# BOOT_JTAG_AUX.net
KiCad netlist of a schematic drawn in Altium Designer
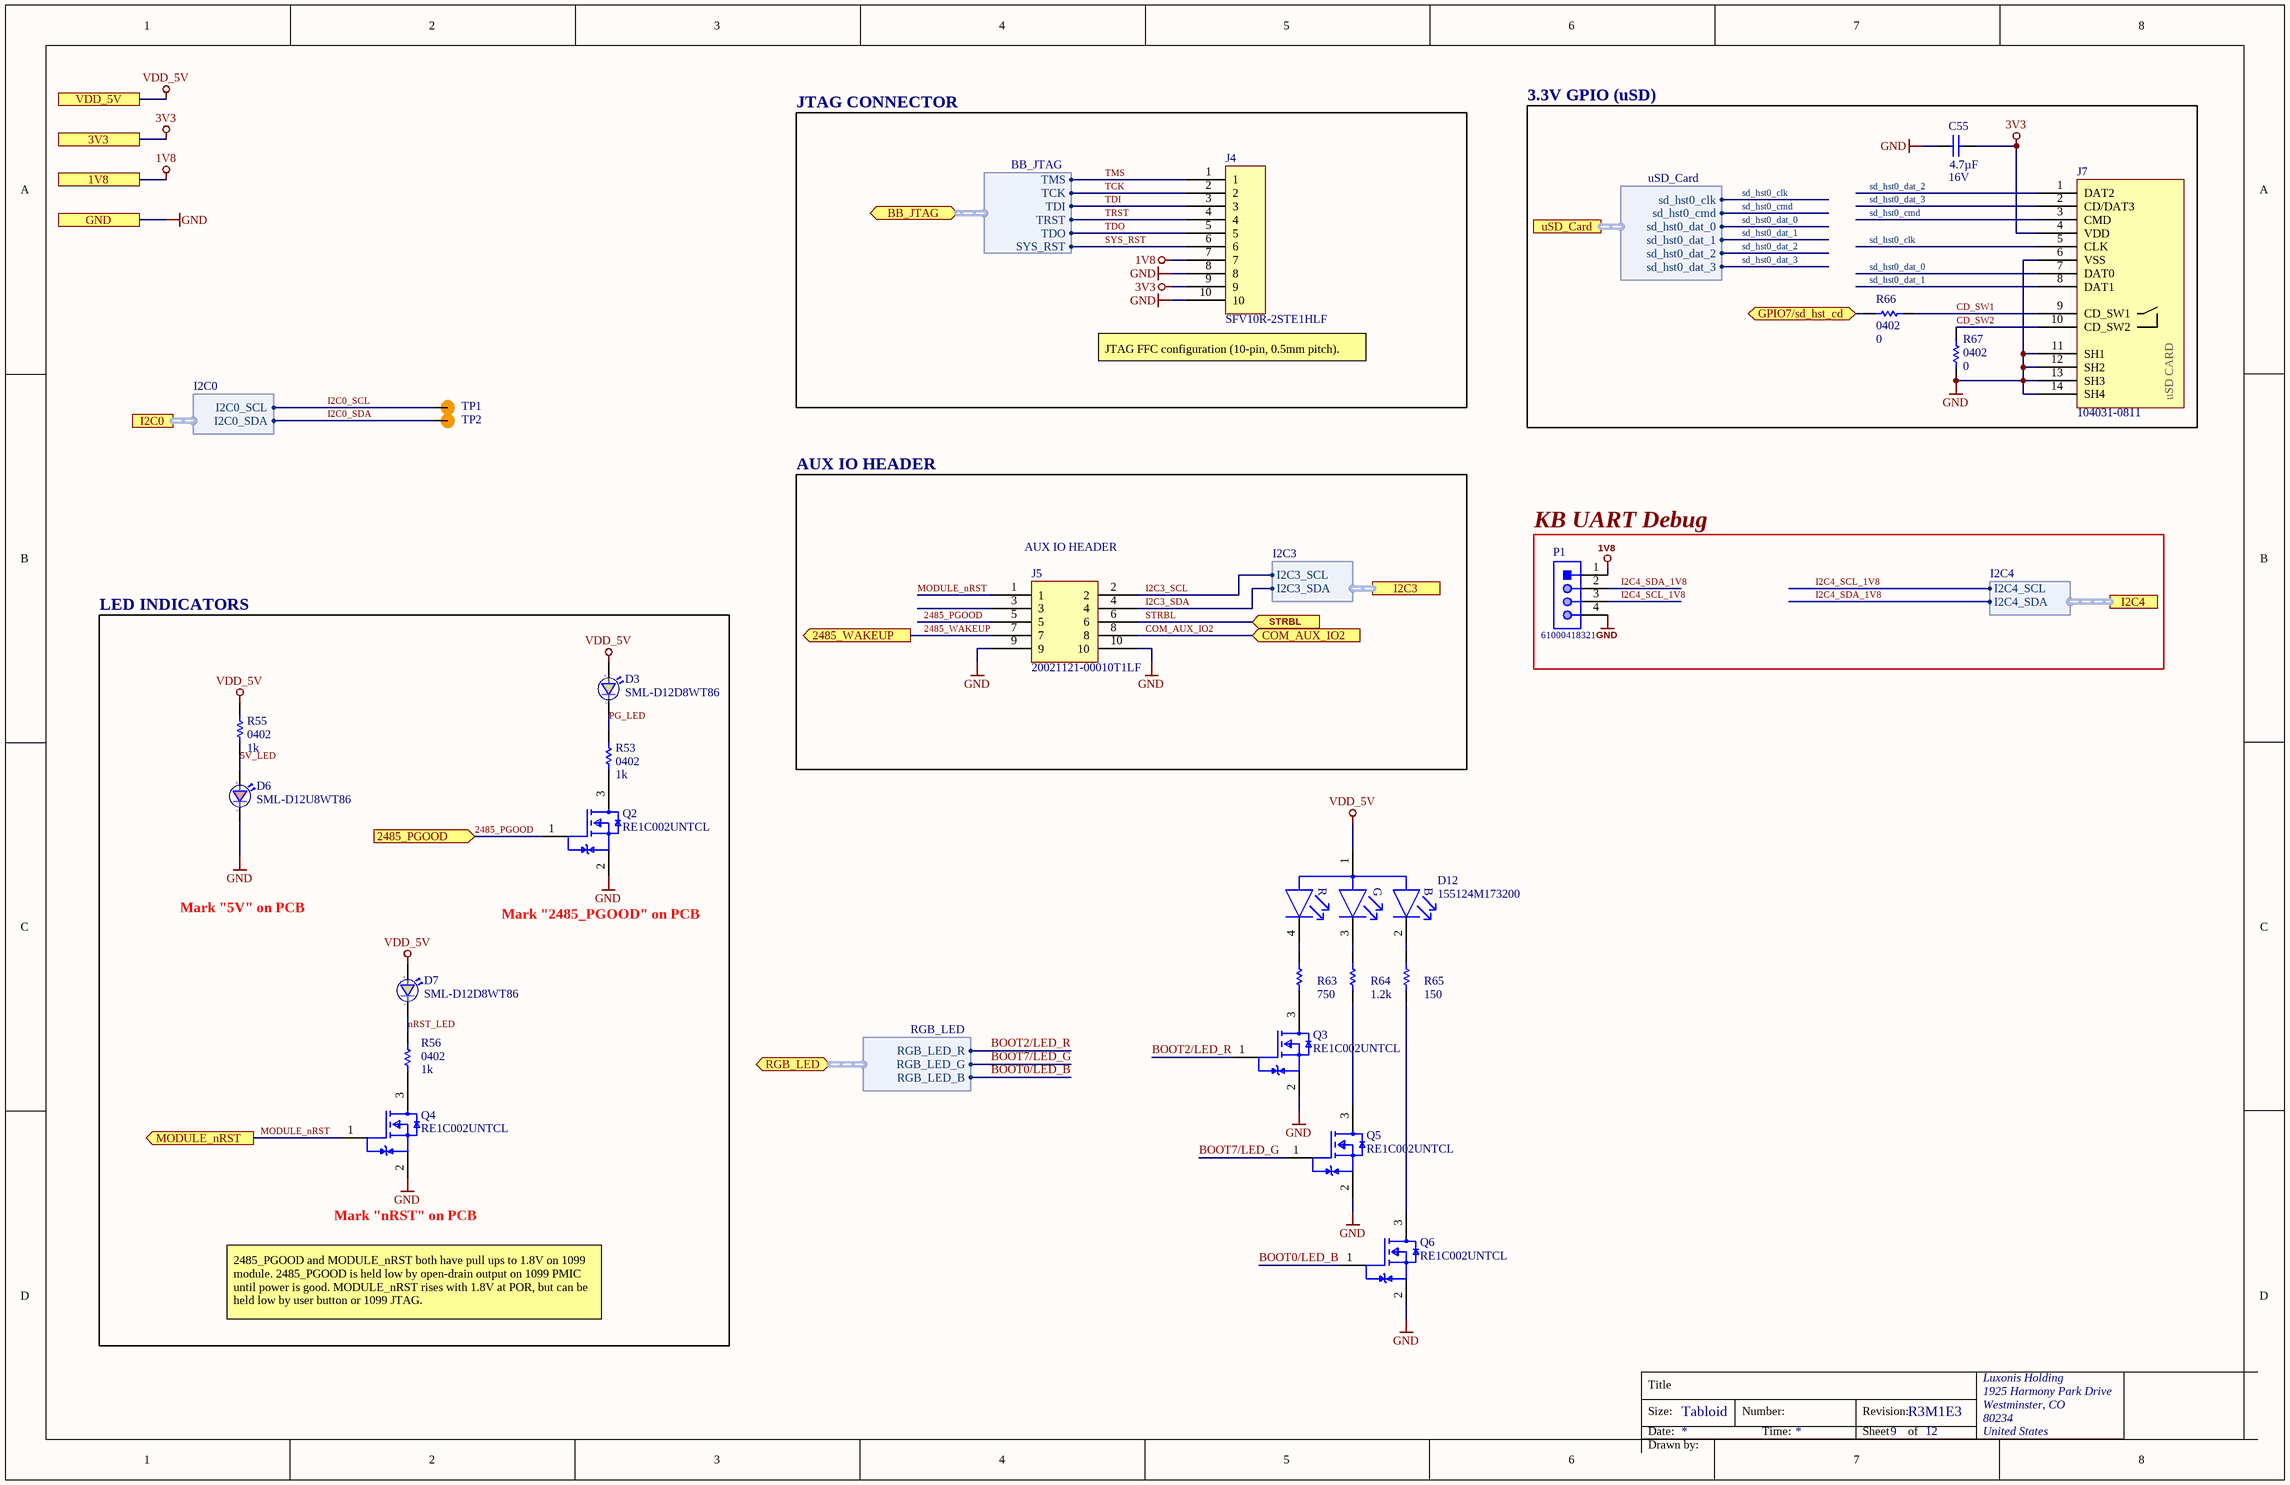
[diagram p0: BOOT_JTAG_AUX.SchDoc]

(export (version "E")
  (design (tool "Eeschema 10.0.6"))
  (components
    (comp (ref "C55")
      (value "4.7µF")
      (footprint "CAPC0603(1608)100_N")
      (description "CAP CER 4.7UF 16V X5R 0603 10%")
      (fields
        (field (name "TOLERANCE") "10%")
        (field (name "VOLTAGE RATING") "16V")
        (field (name "Comment") "GRM188R61C475KAAJD")
      )
      (libsource (lib "Luxonis LLC") (part "LLL153C70G474ME17E"))
    )
    (comp (ref "D3")
      (value "SML-D12D8WT86")
      (footprint "SML_D1xx8W")
      (description "LED ORANGE DIFFUSED 0603 SMD Orange 605nm LED Indication - Discrete 2.2V 0603 (1608 Metric)")
      (libsource (lib "Luxonis LLC") (part "SML-D12D8WT86"))
    )
    (comp (ref "D6")
      (value "SML-D12U8WT86")
      (footprint "SML_D1xx8W")
      (description "LED RED DIFFUSED 0603 SMD Red 620nm LED Indication - Discrete 2.2V 0603 (1608 Metric)")
      (libsource (lib "Luxonis LLC") (part "SML-D12U8WT86"))
    )
    (comp (ref "D7")
      (value "SML-D12D8WT86")
      (footprint "SML_D1xx8W")
      (description "LED ORANGE DIFFUSED 0603 SMD Orange 605nm LED Indication - Discrete 2.2V 0603 (1608 Metric)")
      (libsource (lib "Luxonis LLC") (part "SML-D12D8WT86"))
    )
    (comp (ref "D12")
      (value "155124M173200")
      (footprint "FP-155124M173200-MFG")
      (description "Triple Color LED")
      (libsource (lib "Luxonis LLC") (part "8635049b720462866f33dfa80272b1c"))
    )
    (comp (ref "J4")
      (value "SFV10R-2STE1HLF")
      (footprint "SFV10R-2STE1HLF")
      (description "CONN FFC TOP 10POS 0.50MM R/A")
      (libsource (lib "Luxonis LLC") (part "SFV10R-2STE1HLF"))
    )
    (comp (ref "J5")
      (value "20021121-00010T1LF")
      (footprint "20021121-00010T1LF")
      (description "CONN HEADER SMD 10POS 1.27MM")
      (libsource (lib "Luxonis LLC") (part "20021121-00010T1LF"))
    )
    (comp (ref "J7")
      (value "104031-0811")
      (footprint "104031-0811")
      (description "CONN MICRO SD CARD PUSH-PULL R/A")
      (libsource (lib "Luxonis LLC") (part "104031-0811"))
    )
    (comp (ref "P1")
      (value "61000418321")
      (footprint "61000418321")
      (description "Terminal and Terminal Block")
      (libsource (lib "Luxonis LLC") (part "WE-CN-1P-M-R4"))
    )
    (comp (ref "Q2")
      (value "RE1C002UNTCL")
      (footprint "RE1C002UNTCL")
      (description "MOSFET N-CH 20V 0.2A EMT3")
      (libsource (lib "Luxonis LLC") (part "RE1C002UNTCL"))
    )
    (comp (ref "Q3")
      (value "RE1C002UNTCL")
      (footprint "RE1C002UNTCL")
      (description "MOSFET N-CH 20V 0.2A EMT3")
      (libsource (lib "Luxonis LLC") (part "RE1C002UNTCL"))
    )
    (comp (ref "Q4")
      (value "RE1C002UNTCL")
      (footprint "RE1C002UNTCL")
      (description "MOSFET N-CH 20V 0.2A EMT3")
      (libsource (lib "Luxonis LLC") (part "RE1C002UNTCL"))
    )
    (comp (ref "Q5")
      (value "RE1C002UNTCL")
      (footprint "RE1C002UNTCL")
      (description "MOSFET N-CH 20V 0.2A EMT3")
      (libsource (lib "Luxonis LLC") (part "RE1C002UNTCL"))
    )
    (comp (ref "Q6")
      (value "RE1C002UNTCL")
      (footprint "RE1C002UNTCL")
      (description "MOSFET N-CH 20V 0.2A EMT3")
      (libsource (lib "Luxonis LLC") (part "RE1C002UNTCL"))
    )
    (comp (ref "R53")
      (value "1k")
      (footprint "RESC0402(1005)_N")
      (description "RES SMD 1K OHM 1% 1/16W 0402")
      (fields
        (field (name "CASE/PACKAGE") "0402")
        (field (name "TOLERANCE") "1%")
        (field (name "Comment") "RC0402FR-071KL")
      )
      (libsource (lib "Luxonis LLC") (part "Default resistor symbol"))
    )
    (comp (ref "R55")
      (value "1k")
      (footprint "RESC0402(1005)_N")
      (description "RES SMD 1K OHM 1% 1/16W 0402")
      (fields
        (field (name "CASE/PACKAGE") "0402")
        (field (name "TOLERANCE") "1%")
        (field (name "Comment") "RC0402FR-071KL")
      )
      (libsource (lib "Luxonis LLC") (part "Default resistor symbol"))
    )
    (comp (ref "R56")
      (value "1k")
      (footprint "RESC0402(1005)_N")
      (description "RES SMD 1K OHM 1% 1/16W 0402")
      (fields
        (field (name "CASE/PACKAGE") "0402")
        (field (name "TOLERANCE") "1%")
        (field (name "Comment") "RC0402FR-071KL")
      )
      (libsource (lib "Luxonis LLC") (part "Default resistor symbol"))
    )
    (comp (ref "R63")
      (value "750")
      (footprint "RESC1005X40X25NL05T05")
      (description "RES SMD 750 OHM 1% 0.1W 0402")
      (fields (field (name "TOLERANCE") "1%") (field (name "Comment") "ERJ-2RKF7500X"))
      (libsource (lib "Luxonis LLC") (part "Default resistor symbol"))
    )
    (comp (ref "R64")
      (value "1.2k")
      (footprint "RESC1005X40X25NL05T05")
      (description "RES SMD 1.2K OHM 1% 0.063W 0402")
      (fields (field (name "TOLERANCE") "1%") (field (name "Comment") "CRCW04021K20FKED"))
      (libsource (lib "Luxonis LLC") (part "Default resistor symbol"))
    )
    (comp (ref "R65")
      (value "150")
      (footprint "RESC1005X40X25NL05T10")
      (description "RES SMD 150 OHM 1% 1/16W 0402")
      (fields (field (name "TOLERANCE") "1%") (field (name "Comment") "RC0402FR-07150RL"))
      (libsource (lib "Luxonis LLC") (part "Default resistor symbol"))
    )
    (comp (ref "R66")
      (value "0")
      (footprint "RESC0402(1005)_N")
      (description "RES SMD 0 OHM 5% 1/16W 0402")
      (fields
        (field (name "CASE/PACKAGE") "0402")
        (field (name "TOLERANCE") "5%")
        (field (name "Comment") "CRCW04020000Z0ED")
      )
      (libsource (lib "Luxonis LLC") (part "Default resistor symbol"))
    )
    (comp (ref "R67")
      (value "0")
      (footprint "RESC0402(1005)_N")
      (description "RES SMD 0 OHM 5% 1/16W 0402")
      (fields
        (field (name "CASE/PACKAGE") "0402")
        (field (name "TOLERANCE") "5%")
        (field (name "Comment") "CRCW04020000Z0ED")
      )
      (libsource (lib "Luxonis LLC") (part "Default resistor symbol"))
    )
    (comp (ref "TP1")
      (value "TEST_POINT")
      (footprint "TP100_200_NS")
      (libsource (lib "Luxonis LLC") (part "TEST_POINT"))
    )
    (comp (ref "TP2")
      (value "TEST_POINT")
      (footprint "TP100_200_NS")
      (libsource (lib "Luxonis LLC") (part "TEST_POINT"))
    )
  )
  (nets
    (net (code "7") (name "/5V_LED") (class "Default")
      (node (ref "D6") (pin "2") (pinfunction "A_2") (pintype "passive"))
      (node (ref "R55") (pin "1") (pinfunction "1_1") (pintype "passive"))
    )
    (net (code "8") (name "/2485_PGOOD") (class "Default")
      (node (ref "J5") (pin "5") (pinfunction "5_5") (pintype "passive"))
      (node (ref "Q2") (pin "1") (pinfunction "Gate_1") (pintype "passive"))
    )
    (net (code "9") (name "/2485_WAKEUP") (class "Default")
      (node (ref "J5") (pin "7") (pinfunction "7_7") (pintype "passive"))
    )
    (net (code "10") (name "/BOOT0{slash}LED_B") (class "Default")
      (node (ref "Q6") (pin "1") (pinfunction "Gate_1") (pintype "passive"))
    )
    (net (code "11") (name "/BOOT2{slash}LED_R") (class "Default")
      (node (ref "Q3") (pin "1") (pinfunction "Gate_1") (pintype "passive"))
    )
    (net (code "12") (name "/BOOT7{slash}LED_G") (class "Default")
      (node (ref "Q5") (pin "1") (pinfunction "Gate_1") (pintype "passive"))
    )
    (net (code "13") (name "/CD_SW1") (class "Default")
      (node (ref "J7") (pin "9") (pinfunction "CD_SW1_9") (pintype "passive"))
      (node (ref "R66") (pin "1") (pinfunction "1_1") (pintype "passive"))
    )
    (net (code "14") (name "/CD_SW2") (class "Default")
      (node (ref "J7") (pin "10") (pinfunction "CD_SW2_10") (pintype "passive"))
      (node (ref "R67") (pin "2") (pinfunction "2_2") (pintype "passive"))
    )
    (net (code "15") (name "/COM_AUX_IO2") (class "Default")
      (node (ref "J5") (pin "8") (pinfunction "8_8") (pintype "passive"))
    )
    (net (code "16") (name "/GPIO7{slash}sd_hst_cd") (class "Default")
      (node (ref "R66") (pin "2") (pinfunction "2_2") (pintype "passive"))
    )
    (net (code "17") (name "/I2C0_SCL") (class "Default") (node (ref "TP1") (pin "1") (pintype "passive")))
    (net (code "18") (name "/I2C0_SDA") (class "Default") (node (ref "TP2") (pin "1") (pintype "passive")))
    (net (code "19") (name "/I2C3_SCL") (class "Default")
      (node (ref "J5") (pin "2") (pinfunction "2_2") (pintype "passive"))
    )
    (net (code "20") (name "/I2C3_SDA") (class "Default")
      (node (ref "J5") (pin "4") (pinfunction "4_4") (pintype "passive"))
    )
    (net (code "21") (name "/I2C4_SCL_1V8") (class "Default")
      (node (ref "P1") (pin "3") (pinfunction "3_3") (pintype "passive"))
    )
    (net (code "22") (name "/I2C4_SDA_1V8") (class "Default")
      (node (ref "P1") (pin "2") (pinfunction "2_2") (pintype "passive"))
    )
    (net (code "23") (name "/MODULE_nRST") (class "Default")
      (node (ref "J5") (pin "1") (pinfunction "1_1") (pintype "passive"))
      (node (ref "Q4") (pin "1") (pinfunction "Gate_1") (pintype "passive"))
    )
    (net (code "24") (name "/PG_LED") (class "Default")
      (node (ref "D3") (pin "1") (pinfunction "C_1") (pintype "passive"))
      (node (ref "R53") (pin "2") (pinfunction "2_2") (pintype "passive"))
    )
    (net (code "25") (name "/STRBL") (class "Default")
      (node (ref "J5") (pin "6") (pinfunction "6_6") (pintype "passive"))
    )
    (net (code "26") (name "/SYS_RST") (class "Default")
      (node (ref "J4") (pin "6") (pinfunction "6_6") (pintype "passive"))
    )
    (net (code "27") (name "/TCK") (class "Default")
      (node (ref "J4") (pin "2") (pinfunction "2_2") (pintype "passive"))
    )
    (net (code "28") (name "/TDI") (class "Default")
      (node (ref "J4") (pin "3") (pinfunction "3_3") (pintype "passive"))
    )
    (net (code "29") (name "/TDO") (class "Default")
      (node (ref "J4") (pin "5") (pinfunction "5_5") (pintype "passive"))
    )
    (net (code "30") (name "/TMS") (class "Default")
      (node (ref "J4") (pin "1") (pinfunction "1_1") (pintype "passive"))
    )
    (net (code "31") (name "/TRST") (class "Default")
      (node (ref "J4") (pin "4") (pinfunction "4_4") (pintype "passive"))
    )
    (net (code "32") (name "/nRST_LED") (class "Default")
      (node (ref "D7") (pin "1") (pinfunction "C_1") (pintype "passive"))
      (node (ref "R56") (pin "2") (pinfunction "2_2") (pintype "passive"))
    )
    (net (code "33") (name "/sd_hst0_clk") (class "Default")
      (node (ref "J7") (pin "5") (pinfunction "CLK_5") (pintype "passive"))
    )
    (net (code "34") (name "/sd_hst0_cmd") (class "Default")
      (node (ref "J7") (pin "3") (pinfunction "CMD_3") (pintype "passive"))
    )
    (net (code "35") (name "/sd_hst0_dat_0") (class "Default")
      (node (ref "J7") (pin "7") (pinfunction "DAT0_7") (pintype "passive"))
    )
    (net (code "36") (name "/sd_hst0_dat_1") (class "Default")
      (node (ref "J7") (pin "8") (pinfunction "DAT1_8") (pintype "passive"))
    )
    (net (code "37") (name "/sd_hst0_dat_2") (class "Default")
      (node (ref "J7") (pin "1") (pinfunction "DAT2_1") (pintype "passive"))
    )
    (net (code "38") (name "/sd_hst0_dat_3") (class "Default")
      (node (ref "J7") (pin "2") (pinfunction "CD/DAT3_2") (pintype "passive"))
    )
    (net (code "45") (name "1V8") (class "Default")
      (node (ref "J4") (pin "7") (pinfunction "7_7") (pintype "passive"))
      (node (ref "P1") (pin "1") (pinfunction "1_1") (pintype "passive"))
    )
    (net (code "46") (name "3V3") (class "Default")
      (node (ref "C55") (pin "2") (pinfunction "2_2") (pintype "passive"))
      (node (ref "J4") (pin "9") (pinfunction "9_9") (pintype "passive"))
      (node (ref "J7") (pin "4") (pinfunction "VDD_4") (pintype "passive"))
    )
    (net (code "47") (name "GND") (class "Default")
      (node (ref "C55") (pin "1") (pinfunction "1_1") (pintype "passive"))
      (node (ref "D6") (pin "1") (pinfunction "C_1") (pintype "passive"))
      (node (ref "J4") (pin "10") (pinfunction "10_10") (pintype "passive"))
      (node (ref "J4") (pin "8") (pinfunction "8_8") (pintype "passive"))
      (node (ref "J5") (pin "10") (pinfunction "10_10") (pintype "passive"))
      (node (ref "J5") (pin "9") (pinfunction "9_9") (pintype "passive"))
      (node (ref "J7") (pin "11") (pinfunction "SH1_11") (pintype "passive"))
      (node (ref "J7") (pin "12") (pinfunction "SH2_12") (pintype "passive"))
      (node (ref "J7") (pin "13") (pinfunction "SH3_13") (pintype "passive"))
      (node (ref "J7") (pin "14") (pinfunction "SH4_14") (pintype "passive"))
      (node (ref "J7") (pin "6") (pinfunction "VSS_6") (pintype "passive"))
      (node (ref "P1") (pin "4") (pinfunction "4_4") (pintype "passive"))
      (node (ref "Q2") (pin "2") (pinfunction "Source_2") (pintype "passive"))
      (node (ref "Q3") (pin "2") (pinfunction "Source_2") (pintype "passive"))
      (node (ref "Q4") (pin "2") (pinfunction "Source_2") (pintype "passive"))
      (node (ref "Q5") (pin "2") (pinfunction "Source_2") (pintype "passive"))
      (node (ref "Q6") (pin "2") (pinfunction "Source_2") (pintype "passive"))
      (node (ref "R67") (pin "1") (pinfunction "1_1") (pintype "passive"))
    )
    (net (code "48") (name "Net-(D12-BLUE_C)") (class "Default")
      (node (ref "D12") (pin "2") (pinfunction "BLUE_C_2") (pintype "passive"))
      (node (ref "R65") (pin "2") (pinfunction "2_2") (pintype "passive"))
    )
    (net (code "49") (name "Net-(D12-GREEN_C)") (class "Default")
      (node (ref "D12") (pin "3") (pinfunction "GREEN_C_3") (pintype "passive"))
      (node (ref "R64") (pin "2") (pinfunction "2_2") (pintype "passive"))
    )
    (net (code "50") (name "Net-(D12-RED_C)") (class "Default")
      (node (ref "D12") (pin "4") (pinfunction "RED_C_4") (pintype "passive"))
      (node (ref "R63") (pin "2") (pinfunction "2_2") (pintype "passive"))
    )
    (net (code "51") (name "Net-(Q2-Drain)") (class "Default")
      (node (ref "Q2") (pin "3") (pinfunction "Drain_3") (pintype "passive"))
      (node (ref "R53") (pin "1") (pinfunction "1_1") (pintype "passive"))
    )
    (net (code "52") (name "Net-(Q3-Drain)") (class "Default")
      (node (ref "Q3") (pin "3") (pinfunction "Drain_3") (pintype "passive"))
      (node (ref "R63") (pin "1") (pinfunction "1_1") (pintype "passive"))
    )
    (net (code "53") (name "Net-(Q4-Drain)") (class "Default")
      (node (ref "Q4") (pin "3") (pinfunction "Drain_3") (pintype "passive"))
      (node (ref "R56") (pin "1") (pinfunction "1_1") (pintype "passive"))
    )
    (net (code "54") (name "Net-(Q5-Drain)") (class "Default")
      (node (ref "Q5") (pin "3") (pinfunction "Drain_3") (pintype "passive"))
      (node (ref "R64") (pin "1") (pinfunction "1_1") (pintype "passive"))
    )
    (net (code "55") (name "Net-(Q6-Drain)") (class "Default")
      (node (ref "Q6") (pin "3") (pinfunction "Drain_3") (pintype "passive"))
      (node (ref "R65") (pin "1") (pinfunction "1_1") (pintype "passive"))
    )
    (net (code "56") (name "VDD_5V") (class "Default")
      (node (ref "D12") (pin "1") (pinfunction "COMMON_ANODE_1") (pintype "passive"))
      (node (ref "D3") (pin "2") (pinfunction "A_2") (pintype "passive"))
      (node (ref "D7") (pin "2") (pinfunction "A_2") (pintype "passive"))
      (node (ref "R55") (pin "2") (pinfunction "2_2") (pintype "passive"))
    )
    (net (code "57") (name "unconnected-(J5-Pad3)") (class "Default")
      (node (ref "J5") (pin "3") (pinfunction "3_3") (pintype "passive"))
    )
  )
)
